# 8266_rfid.net
KiCad netlist of a schematic drawn in EAGLE
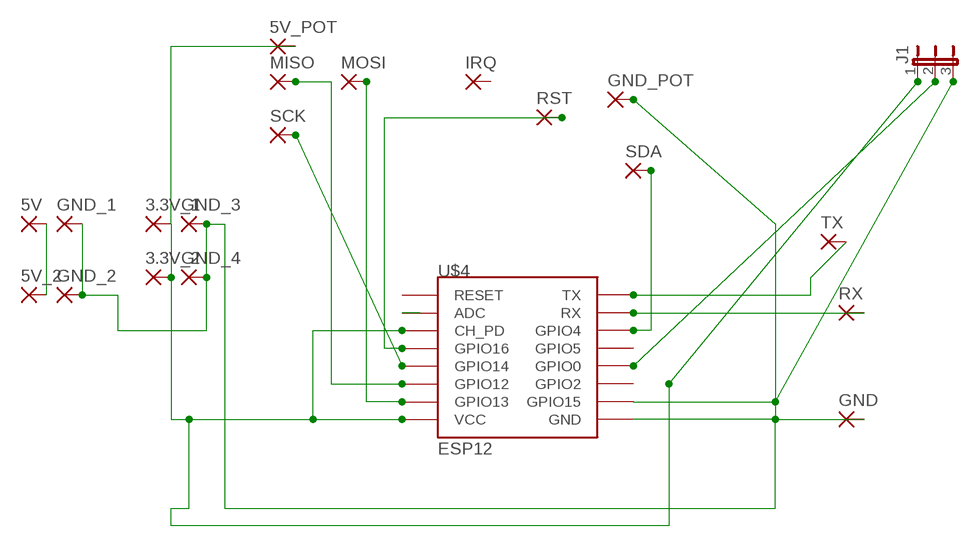
[diagram p0: schematic, sheet 1]

(export (version "E")
  (design (tool "Eeschema 10.0.6"))
  (components
    (comp (ref "3.3V_1")
      (value "2,15/1,0")
      (footprint "eagle-import:2,15_1,0")
      (libsource (lib "eagle-import") (part "2,15/1,0"))
    )
    (comp (ref "3.3V_2")
      (value "2,15/1,0")
      (footprint "eagle-import:2,15_1,0")
      (libsource (lib "eagle-import") (part "2,15/1,0"))
    )
    (comp (ref "5V")
      (value "2,15/1,0")
      (footprint "eagle-import:2,15_1,0")
      (libsource (lib "eagle-import") (part "2,15/1,0"))
    )
    (comp (ref "5V_2")
      (value "2,15/1,0")
      (footprint "eagle-import:2,15_1,0")
      (libsource (lib "eagle-import") (part "2,15/1,0"))
    )
    (comp (ref "5V_POT")
      (value "2,15/1,0")
      (footprint "eagle-import:2,15_1,0")
      (libsource (lib "eagle-import") (part "2,15/1,0"))
    )
    (comp (ref "GND")
      (value "2,15/1,0")
      (footprint "eagle-import:2,15_1,0")
      (libsource (lib "eagle-import") (part "2,15/1,0"))
    )
    (comp (ref "GND_1")
      (value "2,15/1,0")
      (footprint "eagle-import:2,15_1,0")
      (libsource (lib "eagle-import") (part "2,15/1,0"))
    )
    (comp (ref "GND_2")
      (value "2,15/1,0")
      (footprint "eagle-import:2,15_1,0")
      (libsource (lib "eagle-import") (part "2,15/1,0"))
    )
    (comp (ref "GND_3")
      (value "2,15/1,0")
      (footprint "eagle-import:2,15_1,0")
      (libsource (lib "eagle-import") (part "2,15/1,0"))
    )
    (comp (ref "GND_4")
      (value "2,15/1,0")
      (footprint "eagle-import:2,15_1,0")
      (libsource (lib "eagle-import") (part "2,15/1,0"))
    )
    (comp (ref "GND_POT")
      (value "2,15/1,0")
      (footprint "eagle-import:2,15_1,0")
      (libsource (lib "eagle-import") (part "2,15/1,0"))
    )
    (comp (ref "IRQ")
      (value "2,15/1,0")
      (footprint "eagle-import:2,15_1,0")
      (libsource (lib "eagle-import") (part "2,15/1,0"))
    )
    (comp (ref "J1")
      (value "JP2E")
      (footprint "eagle-import:JP2")
      (libsource (lib "eagle-import") (part "JP2E"))
    )
    (comp (ref "MISO")
      (value "2,15/1,0")
      (footprint "eagle-import:2,15_1,0")
      (libsource (lib "eagle-import") (part "2,15/1,0"))
    )
    (comp (ref "MOSI")
      (value "2,15/1,0")
      (footprint "eagle-import:2,15_1,0")
      (libsource (lib "eagle-import") (part "2,15/1,0"))
    )
    (comp (ref "RST")
      (value "2,15/1,0")
      (footprint "eagle-import:2,15_1,0")
      (libsource (lib "eagle-import") (part "2,15/1,0"))
    )
    (comp (ref "RX")
      (value "2,15/1,0")
      (footprint "eagle-import:2,15_1,0")
      (libsource (lib "eagle-import") (part "2,15/1,0"))
    )
    (comp (ref "SCK")
      (value "2,15/1,0")
      (footprint "eagle-import:2,15_1,0")
      (libsource (lib "eagle-import") (part "2,15/1,0"))
    )
    (comp (ref "SDA")
      (value "2,15/1,0")
      (footprint "eagle-import:2,15_1,0")
      (libsource (lib "eagle-import") (part "2,15/1,0"))
    )
    (comp (ref "TX")
      (value "2,15/1,0")
      (footprint "eagle-import:2,15_1,0")
      (libsource (lib "eagle-import") (part "2,15/1,0"))
    )
    (comp (ref "U$4")
      (value "ESP12")
      (footprint "eagle-import:ESP12")
      (libsource (lib "eagle-import") (part "ESP12"))
    )
  )
  (nets
    (net (code "1") (name "/5V") (class "Default")
      (node (ref "5V") (pin "1") (pinfunction "P_1") (pintype "passive"))
      (node (ref "5V_2") (pin "1") (pinfunction "P_1") (pintype "passive"))
      (node (ref "GND") (pin "1") (pinfunction "P_1") (pintype "passive"))
      (node (ref "GND_1") (pin "1") (pinfunction "P_1") (pintype "passive"))
      (node (ref "GND_2") (pin "1") (pinfunction "P_1") (pintype "passive"))
      (node (ref "GND_3") (pin "1") (pinfunction "P_1") (pintype "passive"))
      (node (ref "GND_4") (pin "1") (pinfunction "P_1") (pintype "passive"))
      (node (ref "GND_POT") (pin "1") (pinfunction "P_1") (pintype "passive"))
      (node (ref "J1") (pin "3") (pinfunction "3_3") (pintype "passive"))
      (node (ref "U$4") (pin "GND") (pinfunction "GND_GND") (pintype "bidirectional"))
      (node (ref "U$4") (pin "GPIO15") (pinfunction "GPIO15_GPIO15") (pintype "bidirectional"))
    )
    (net (code "2") (name "Net-(3.3V_1-P)") (class "Default")
      (node (ref "3.3V_1") (pin "1") (pinfunction "P_1") (pintype "passive"))
      (node (ref "3.3V_2") (pin "1") (pinfunction "P_1") (pintype "passive"))
      (node (ref "5V_POT") (pin "1") (pinfunction "P_1") (pintype "passive"))
      (node (ref "J1") (pin "1") (pinfunction "1_1") (pintype "passive"))
      (node (ref "U$4") (pin "CH_PD") (pinfunction "CH_PD_CH_PD") (pintype "bidirectional"))
      (node (ref "U$4") (pin "VCC") (pinfunction "VCC_VCC") (pintype "bidirectional"))
    )
    (net (code "3") (name "Net-(J1-Pad2)") (class "Default")
      (node (ref "J1") (pin "2") (pinfunction "2_2") (pintype "passive"))
      (node (ref "U$4") (pin "GPIO0") (pinfunction "GPIO0_GPIO0") (pintype "bidirectional"))
    )
    (net (code "4") (name "Net-(MISO-P)") (class "Default")
      (node (ref "MISO") (pin "1") (pinfunction "P_1") (pintype "passive"))
      (node (ref "U$4") (pin "GPIO12") (pinfunction "GPIO12_GPIO12") (pintype "bidirectional"))
    )
    (net (code "5") (name "Net-(MOSI-P)") (class "Default")
      (node (ref "MOSI") (pin "1") (pinfunction "P_1") (pintype "passive"))
      (node (ref "U$4") (pin "GPIO13") (pinfunction "GPIO13_GPIO13") (pintype "bidirectional"))
    )
    (net (code "6") (name "Net-(RST-P)") (class "Default")
      (node (ref "RST") (pin "1") (pinfunction "P_1") (pintype "passive"))
      (node (ref "U$4") (pin "GPIO16") (pinfunction "GPIO16_GPIO16") (pintype "bidirectional"))
    )
    (net (code "7") (name "Net-(RX-P)") (class "Default")
      (node (ref "RX") (pin "1") (pinfunction "P_1") (pintype "passive"))
      (node (ref "U$4") (pin "RX") (pinfunction "RX_RX") (pintype "bidirectional"))
    )
    (net (code "8") (name "Net-(SCK-P)") (class "Default")
      (node (ref "SCK") (pin "1") (pinfunction "P_1") (pintype "passive"))
      (node (ref "U$4") (pin "GPIO14") (pinfunction "GPIO14_GPIO14") (pintype "bidirectional"))
    )
    (net (code "9") (name "Net-(SDA-P)") (class "Default")
      (node (ref "SDA") (pin "1") (pinfunction "P_1") (pintype "passive"))
      (node (ref "U$4") (pin "GPIO4") (pinfunction "GPIO4_GPIO4") (pintype "bidirectional"))
    )
    (net (code "10") (name "Net-(TX-P)") (class "Default")
      (node (ref "TX") (pin "1") (pinfunction "P_1") (pintype "passive"))
      (node (ref "U$4") (pin "TX") (pinfunction "TX_TX") (pintype "bidirectional"))
    )
    (net (code "11") (name "unconnected-(IRQ-P-Pad1)") (class "Default")
      (node (ref "IRQ") (pin "1") (pinfunction "P_1") (pintype "passive"))
    )
    (net (code "12") (name "unconnected-(U$4-PadADC)") (class "Default")
      (node (ref "U$4") (pin "ADC") (pinfunction "ADC_ADC") (pintype "bidirectional"))
    )
    (net (code "13") (name "unconnected-(U$4-PadGPIO2)") (class "Default")
      (node (ref "U$4") (pin "GPIO2") (pinfunction "GPIO2_GPIO2") (pintype "bidirectional"))
    )
    (net (code "14") (name "unconnected-(U$4-PadGPIO5)") (class "Default")
      (node (ref "U$4") (pin "GPIO5") (pinfunction "GPIO5_GPIO5") (pintype "bidirectional"))
    )
    (net (code "15") (name "unconnected-(U$4-PadRESET)") (class "Default")
      (node (ref "U$4") (pin "RESET") (pinfunction "RESET_RESET") (pintype "bidirectional"))
    )
  )
)
